# CORE.net
KiCad netlist of a schematic drawn in Altium Designer
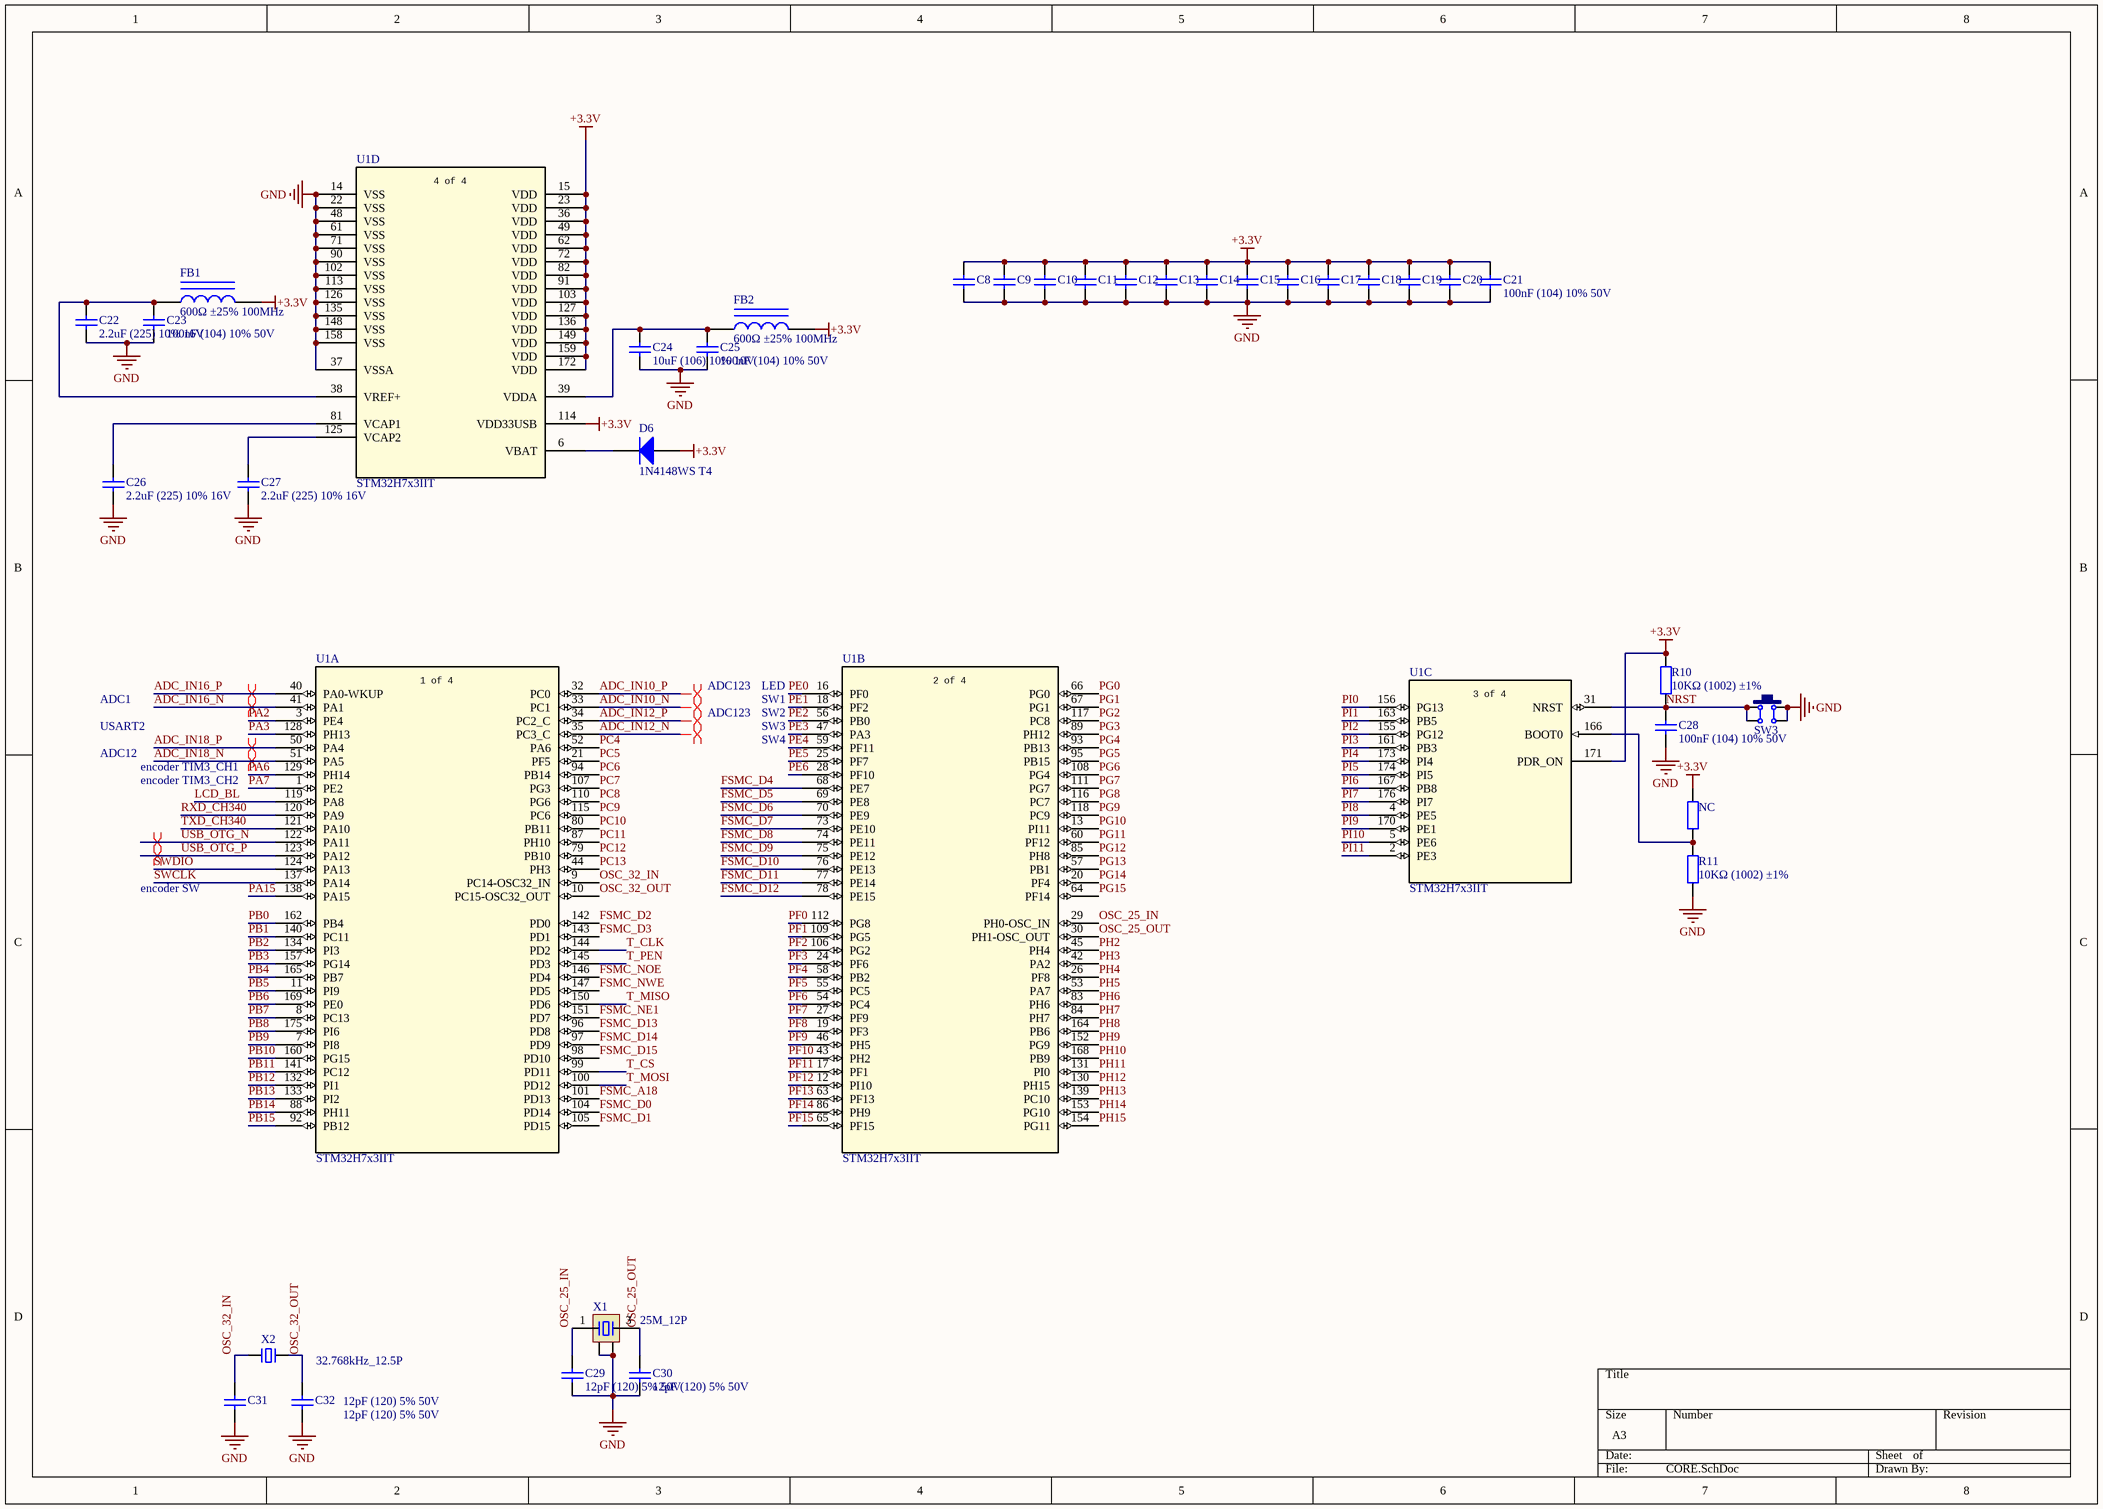
[diagram p0: CORE.SchDoc]

(export (version "E")
  (design (tool "Eeschema 10.0.6"))
  (components
    (comp (ref "C8")
      (value "100nF (104) 10% 50V")
      (footprint "0603_C")
      (description "贴片电容")
      (libsource (lib "Cap") (part "0603 100nF (104) 10% 50V"))
    )
    (comp (ref "C9")
      (value "100nF (104) 10% 50V")
      (footprint "0603_C")
      (description "贴片电容")
      (libsource (lib "Cap") (part "0603 100nF (104) 10% 50V"))
    )
    (comp (ref "C10")
      (value "100nF (104) 10% 50V")
      (footprint "0603_C")
      (description "贴片电容")
      (libsource (lib "Cap") (part "0603 100nF (104) 10% 50V"))
    )
    (comp (ref "C11")
      (value "100nF (104) 10% 50V")
      (footprint "0603_C")
      (description "贴片电容")
      (libsource (lib "Cap") (part "0603 100nF (104) 10% 50V"))
    )
    (comp (ref "C12")
      (value "100nF (104) 10% 50V")
      (footprint "0603_C")
      (description "贴片电容")
      (libsource (lib "Cap") (part "0603 100nF (104) 10% 50V"))
    )
    (comp (ref "C13")
      (value "100nF (104) 10% 50V")
      (footprint "0603_C")
      (description "贴片电容")
      (libsource (lib "Cap") (part "0603 100nF (104) 10% 50V"))
    )
    (comp (ref "C14")
      (value "100nF (104) 10% 50V")
      (footprint "0603_C")
      (description "贴片电容")
      (libsource (lib "Cap") (part "0603 100nF (104) 10% 50V"))
    )
    (comp (ref "C15")
      (value "100nF (104) 10% 50V")
      (footprint "0603_C")
      (description "贴片电容")
      (libsource (lib "Cap") (part "0603 100nF (104) 10% 50V"))
    )
    (comp (ref "C16")
      (value "100nF (104) 10% 50V")
      (footprint "0603_C")
      (description "贴片电容")
      (libsource (lib "Cap") (part "0603 100nF (104) 10% 50V"))
    )
    (comp (ref "C17")
      (value "100nF (104) 10% 50V")
      (footprint "0603_C")
      (description "贴片电容")
      (libsource (lib "Cap") (part "0603 100nF (104) 10% 50V"))
    )
    (comp (ref "C18")
      (value "100nF (104) 10% 50V")
      (footprint "0603_C")
      (description "贴片电容")
      (libsource (lib "Cap") (part "0603 100nF (104) 10% 50V"))
    )
    (comp (ref "C19")
      (value "100nF (104) 10% 50V")
      (footprint "0603_C")
      (description "贴片电容")
      (libsource (lib "Cap") (part "0603 100nF (104) 10% 50V"))
    )
    (comp (ref "C20")
      (value "100nF (104) 10% 50V")
      (footprint "0603_C")
      (description "贴片电容")
      (libsource (lib "Cap") (part "0603 100nF (104) 10% 50V"))
    )
    (comp (ref "C21")
      (value "100nF (104) 10% 50V")
      (footprint "0603_C")
      (description "贴片电容")
      (libsource (lib "Cap") (part "0603 100nF (104) 10% 50V"))
    )
    (comp (ref "C22")
      (value "2.2uF (225) 10% 16V")
      (footprint "0603_C")
      (description "贴片电容")
      (libsource (lib "Cap") (part "0603 2.2uF (225) 10% 16V"))
    )
    (comp (ref "C23")
      (value "100nF (104) 10% 50V")
      (footprint "0603_C")
      (description "贴片电容")
      (libsource (lib "Cap") (part "0603 100nF (104) 10% 50V"))
    )
    (comp (ref "C24")
      (value "10uF (106) 10% 10V")
      (footprint "0603_C")
      (description "贴片电容")
      (libsource (lib "Cap") (part "0603 10uF (106) 10% 10V"))
    )
    (comp (ref "C25")
      (value "100nF (104) 10% 50V")
      (footprint "0603_C")
      (description "贴片电容")
      (libsource (lib "Cap") (part "0603 100nF (104) 10% 50V"))
    )
    (comp (ref "C26")
      (value "2.2uF (225) 10% 16V")
      (footprint "0603_C")
      (description "贴片电容")
      (libsource (lib "Cap") (part "0603 2.2uF (225) 10% 16V"))
    )
    (comp (ref "C27")
      (value "2.2uF (225) 10% 16V")
      (footprint "0603_C")
      (description "贴片电容")
      (libsource (lib "Cap") (part "0603 2.2uF (225) 10% 16V"))
    )
    (comp (ref "C28")
      (value "100nF (104) 10% 50V")
      (footprint "0603_C")
      (description "贴片电容")
      (libsource (lib "Cap") (part "0603 100nF (104) 10% 50V"))
    )
    (comp (ref "C29")
      (value "12pF (120) 5% 50V")
      (footprint "0603_C")
      (description "贴片电容")
      (libsource (lib "Cap") (part "0603 12pF (120) 5% 50V"))
    )
    (comp (ref "C30")
      (value "12pF (120) 5% 50V")
      (footprint "0603_C")
      (description "贴片电容")
      (libsource (lib "Cap") (part "0603 12pF (120) 5% 50V"))
    )
    (comp (ref "C31")
      (value "12pF (120) 5% 50V")
      (footprint "0603_C")
      (description "贴片电容")
      (libsource (lib "Cap") (part "0603 12pF (120) 5% 50V"))
    )
    (comp (ref "C32")
      (value "12pF (120) 5% 50V")
      (footprint "0603_C")
      (description "贴片电容")
      (libsource (lib "Cap") (part "0603 12pF (120) 5% 50V"))
    )
    (comp (ref "D6")
      (value "1N4148WS T4")
      (footprint "SOD-323")
      (description "二极管")
      (libsource (lib "Diode") (part "SOD-323 1N4148WS T4"))
    )
    (comp (ref "FB1")
      (value "600Ω ±25% 100MHz")
      (footprint "0805_L")
      (description "贴片磁珠")
      (libsource (lib "IUD") (part "0805 600Ω 25% 100MHz"))
    )
    (comp (ref "FB2")
      (value "600Ω ±25% 100MHz")
      (footprint "0805_L")
      (description "贴片磁珠")
      (libsource (lib "IUD") (part "0805 600Ω 25% 100MHz"))
    )
    (comp (ref "NC")
      (value "~")
      (footprint "0603_R")
      (description "贴片电阻")
      (libsource (lib "RES") (part "0603 0Ω (0R0) 1%"))
    )
    (comp (ref "R10")
      (value "10KΩ (1002) ±1%")
      (footprint "0603_R")
      (description "贴片电阻")
      (libsource (lib "RES") (part "0603 10KΩ (1002) 1%"))
    )
    (comp (ref "R11")
      (value "10KΩ (1002) ±1%")
      (footprint "0603_R")
      (description "贴片电阻")
      (libsource (lib "RES") (part "0603 10KΩ (1002) 1%"))
    )
    (comp (ref "SW3")
      (value "6x6x5")
      (footprint "TSW DIP-6*6*6")
      (description "直插6x6轻触开关")
      (fields (field (name "版权归属") "源创客"))
      (libsource (lib "5.1   - 按键-开关") (part "TSW DIP-6x6"))
    )
    (comp (ref "U1")
      (value "STM32H7x3IIT")
      (footprint "LQFP176_24x24mm")
      (description "Imported")
      (fields
        (field (name "MANUFACTURER_PART_NUMBER") "stm32h7x3iit")
        (field (name "COPYRIGHT") "Copyright (C) 2016 Accelerated Designs. All rights reserved")
      )
      (libsource (lib "") (part "STM32H7x3IIT_3"))
    )
    (comp (ref "X1")
      (value "25M_12P")
      (footprint "OSC 3225-4P")
      (description "4脚无源晶振")
      (fields (field (name "版权归属") "源创客"))
      (libsource (lib "10.1 - 保险丝-晶振") (part "XTAL-4P"))
    )
    (comp (ref "X2")
      (value "32.768kHz_12.5P")
      (footprint "OSC 3215-2P")
      (description "2脚无源脚晶振")
      (fields (field (name "版权归属") "源创客"))
      (libsource (lib "10.1 - 保险丝-晶振") (part "XTAL-2P"))
    )
  )
  (nets
    (net (code "1") (name "+3.3V") (class "Default")
      (node (ref "C10") (pin "2") (pinfunction "2_2") (pintype "passive"))
      (node (ref "C11") (pin "2") (pinfunction "2_2") (pintype "passive"))
      (node (ref "C12") (pin "2") (pinfunction "2_2") (pintype "passive"))
      (node (ref "C13") (pin "2") (pinfunction "2_2") (pintype "passive"))
      (node (ref "C14") (pin "2") (pinfunction "2_2") (pintype "passive"))
      (node (ref "C15") (pin "2") (pinfunction "2_2") (pintype "passive"))
      (node (ref "C16") (pin "2") (pinfunction "2_2") (pintype "passive"))
      (node (ref "C17") (pin "2") (pinfunction "2_2") (pintype "passive"))
      (node (ref "C18") (pin "2") (pinfunction "2_2") (pintype "passive"))
      (node (ref "C19") (pin "2") (pinfunction "2_2") (pintype "passive"))
      (node (ref "C20") (pin "2") (pinfunction "2_2") (pintype "passive"))
      (node (ref "C21") (pin "2") (pinfunction "2_2") (pintype "passive"))
      (node (ref "C8") (pin "2") (pinfunction "2_2") (pintype "passive"))
      (node (ref "C9") (pin "2") (pinfunction "2_2") (pintype "passive"))
      (node (ref "D6") (pin "1") (pinfunction "A_1") (pintype "passive"))
      (node (ref "FB1") (pin "2") (pinfunction "2_2") (pintype "passive"))
      (node (ref "FB2") (pin "2") (pinfunction "2_2") (pintype "passive"))
      (node (ref "NC") (pin "1") (pinfunction "1_1") (pintype "passive"))
      (node (ref "R10") (pin "2") (pinfunction "2_2") (pintype "passive"))
      (node (ref "U1") (pin "103") (pinfunction "VDD_103") (pintype "power_in"))
      (node (ref "U1") (pin "114") (pinfunction "VDD33USB_114") (pintype "power_in"))
      (node (ref "U1") (pin "127") (pinfunction "VDD_127") (pintype "power_in"))
      (node (ref "U1") (pin "136") (pinfunction "VDD_136") (pintype "power_in"))
      (node (ref "U1") (pin "149") (pinfunction "VDD_149") (pintype "power_in"))
      (node (ref "U1") (pin "15") (pinfunction "VDD_15") (pintype "power_in"))
      (node (ref "U1") (pin "159") (pinfunction "VDD_159") (pintype "power_in"))
      (node (ref "U1") (pin "171") (pinfunction "PDR_ON_171") (pintype "passive"))
      (node (ref "U1") (pin "172") (pinfunction "VDD_172") (pintype "power_in"))
      (node (ref "U1") (pin "23") (pinfunction "VDD_23") (pintype "power_in"))
      (node (ref "U1") (pin "36") (pinfunction "VDD_36") (pintype "power_in"))
      (node (ref "U1") (pin "49") (pinfunction "VDD_49") (pintype "power_in"))
      (node (ref "U1") (pin "62") (pinfunction "VDD_62") (pintype "power_in"))
      (node (ref "U1") (pin "72") (pinfunction "VDD_72") (pintype "power_in"))
      (node (ref "U1") (pin "82") (pinfunction "VDD_82") (pintype "power_in"))
      (node (ref "U1") (pin "91") (pinfunction "VDD_91") (pintype "power_in"))
    )
    (net (code "2") (name "/ADC_IN10_N") (class "Default")
      (node (ref "U1") (pin "33") (pinfunction "PC1_33") (pintype "bidirectional"))
    )
    (net (code "3") (name "/ADC_IN10_P") (class "Default")
      (node (ref "U1") (pin "32") (pinfunction "PC0_32") (pintype "bidirectional"))
    )
    (net (code "4") (name "/ADC_IN12_N") (class "Default")
      (node (ref "U1") (pin "35") (pinfunction "PC3_C_35") (pintype "bidirectional"))
    )
    (net (code "5") (name "/ADC_IN12_P") (class "Default")
      (node (ref "U1") (pin "34") (pinfunction "PC2_C_34") (pintype "bidirectional"))
    )
    (net (code "6") (name "/ADC_IN16_N") (class "Default")
      (node (ref "U1") (pin "41") (pinfunction "PA1_41") (pintype "bidirectional"))
    )
    (net (code "7") (name "/ADC_IN16_P") (class "Default")
      (node (ref "U1") (pin "40") (pinfunction "PA0-WKUP_40") (pintype "bidirectional"))
    )
    (net (code "8") (name "/ADC_IN18_N") (class "Default")
      (node (ref "U1") (pin "51") (pinfunction "PA5_51") (pintype "bidirectional"))
    )
    (net (code "9") (name "/ADC_IN18_P") (class "Default")
      (node (ref "U1") (pin "50") (pinfunction "PA4_50") (pintype "bidirectional"))
    )
    (net (code "10") (name "/FSMC_A18") (class "Default")
      (node (ref "U1") (pin "101") (pinfunction "PD13_101") (pintype "bidirectional"))
    )
    (net (code "11") (name "/FSMC_D0") (class "Default")
      (node (ref "U1") (pin "104") (pinfunction "PD14_104") (pintype "bidirectional"))
    )
    (net (code "12") (name "/FSMC_D1") (class "Default")
      (node (ref "U1") (pin "105") (pinfunction "PD15_105") (pintype "bidirectional"))
    )
    (net (code "13") (name "/FSMC_D2") (class "Default")
      (node (ref "U1") (pin "142") (pinfunction "PD0_142") (pintype "bidirectional"))
    )
    (net (code "14") (name "/FSMC_D3") (class "Default")
      (node (ref "U1") (pin "143") (pinfunction "PD1_143") (pintype "bidirectional"))
    )
    (net (code "15") (name "/FSMC_D4") (class "Default")
      (node (ref "U1") (pin "68") (pinfunction "PE7_68") (pintype "bidirectional"))
    )
    (net (code "16") (name "/FSMC_D5") (class "Default")
      (node (ref "U1") (pin "69") (pinfunction "PE8_69") (pintype "bidirectional"))
    )
    (net (code "17") (name "/FSMC_D6") (class "Default")
      (node (ref "U1") (pin "70") (pinfunction "PE9_70") (pintype "bidirectional"))
    )
    (net (code "18") (name "/FSMC_D7") (class "Default")
      (node (ref "U1") (pin "73") (pinfunction "PE10_73") (pintype "bidirectional"))
    )
    (net (code "19") (name "/FSMC_D8") (class "Default")
      (node (ref "U1") (pin "74") (pinfunction "PE11_74") (pintype "bidirectional"))
    )
    (net (code "20") (name "/FSMC_D9") (class "Default")
      (node (ref "U1") (pin "75") (pinfunction "PE12_75") (pintype "bidirectional"))
    )
    (net (code "21") (name "/FSMC_D10") (class "Default")
      (node (ref "U1") (pin "76") (pinfunction "PE13_76") (pintype "bidirectional"))
    )
    (net (code "22") (name "/FSMC_D11") (class "Default")
      (node (ref "U1") (pin "77") (pinfunction "PE14_77") (pintype "bidirectional"))
    )
    (net (code "23") (name "/FSMC_D12") (class "Default")
      (node (ref "U1") (pin "78") (pinfunction "PE15_78") (pintype "bidirectional"))
    )
    (net (code "24") (name "/FSMC_D13") (class "Default")
      (node (ref "U1") (pin "96") (pinfunction "PD8_96") (pintype "bidirectional"))
    )
    (net (code "25") (name "/FSMC_D14") (class "Default")
      (node (ref "U1") (pin "97") (pinfunction "PD9_97") (pintype "bidirectional"))
    )
    (net (code "26") (name "/FSMC_D15") (class "Default")
      (node (ref "U1") (pin "98") (pinfunction "PD10_98") (pintype "bidirectional"))
    )
    (net (code "27") (name "/FSMC_NE1") (class "Default")
      (node (ref "U1") (pin "151") (pinfunction "PD7_151") (pintype "bidirectional"))
    )
    (net (code "28") (name "/FSMC_NOE") (class "Default")
      (node (ref "U1") (pin "146") (pinfunction "PD4_146") (pintype "bidirectional"))
    )
    (net (code "29") (name "/FSMC_NWE") (class "Default")
      (node (ref "U1") (pin "147") (pinfunction "PD5_147") (pintype "bidirectional"))
    )
    (net (code "30") (name "/LCD_BL") (class "Default")
      (node (ref "U1") (pin "119") (pinfunction "PA8_119") (pintype "bidirectional"))
    )
    (net (code "31") (name "/NRST") (class "Default")
      (node (ref "C28") (pin "2") (pinfunction "2_2") (pintype "passive"))
      (node (ref "R10") (pin "1") (pinfunction "1_1") (pintype "passive"))
      (node (ref "SW3") (pin "1") (pinfunction "1_1") (pintype "passive"))
      (node (ref "SW3") (pin "4") (pinfunction "4_4") (pintype "passive"))
      (node (ref "U1") (pin "31") (pinfunction "NRST_31") (pintype "bidirectional"))
    )
    (net (code "32") (name "/OSC_25_IN") (class "Default")
      (node (ref "C29") (pin "2") (pinfunction "2_2") (pintype "passive"))
      (node (ref "U1") (pin "29") (pinfunction "PH0-OSC_IN_29") (pintype "bidirectional"))
      (node (ref "X1") (pin "1") (pinfunction "1_1") (pintype "passive"))
    )
    (net (code "33") (name "/OSC_25_OUT") (class "Default")
      (node (ref "C30") (pin "1") (pinfunction "1_1") (pintype "passive"))
      (node (ref "U1") (pin "30") (pinfunction "PH1-OSC_OUT_30") (pintype "bidirectional"))
      (node (ref "X1") (pin "3") (pinfunction "3_3") (pintype "passive"))
    )
    (net (code "34") (name "/OSC_32_IN") (class "Default")
      (node (ref "C31") (pin "2") (pinfunction "2_2") (pintype "passive"))
      (node (ref "U1") (pin "9") (pinfunction "PC14-OSC32_IN_9") (pintype "bidirectional"))
      (node (ref "X2") (pin "1") (pinfunction "1_1") (pintype "passive"))
    )
    (net (code "35") (name "/OSC_32_OUT") (class "Default")
      (node (ref "C32") (pin "2") (pinfunction "2_2") (pintype "passive"))
      (node (ref "U1") (pin "10") (pinfunction "PC15-OSC32_OUT_10") (pintype "bidirectional"))
      (node (ref "X2") (pin "2") (pinfunction "2_2") (pintype "passive"))
    )
    (net (code "36") (name "/PA2") (class "Default")
      (node (ref "U1") (pin "3") (pinfunction "PE4_3") (pintype "bidirectional"))
    )
    (net (code "37") (name "/PA3") (class "Default")
      (node (ref "U1") (pin "128") (pinfunction "PH13_128") (pintype "bidirectional"))
    )
    (net (code "38") (name "/PA6") (class "Default")
      (node (ref "U1") (pin "129") (pinfunction "PH14_129") (pintype "bidirectional"))
    )
    (net (code "39") (name "/PA7") (class "Default")
      (node (ref "U1") (pin "1") (pinfunction "PE2_1") (pintype "bidirectional"))
    )
    (net (code "40") (name "/PA15") (class "Default")
      (node (ref "U1") (pin "138") (pinfunction "PA15_138") (pintype "bidirectional"))
    )
    (net (code "41") (name "/PB0") (class "Default")
      (node (ref "U1") (pin "162") (pinfunction "PB4_162") (pintype "bidirectional"))
    )
    (net (code "42") (name "/PB1") (class "Default")
      (node (ref "U1") (pin "140") (pinfunction "PC11_140") (pintype "bidirectional"))
    )
    (net (code "43") (name "/PB2") (class "Default")
      (node (ref "U1") (pin "134") (pinfunction "PI3_134") (pintype "bidirectional"))
    )
    (net (code "44") (name "/PB3") (class "Default")
      (node (ref "U1") (pin "157") (pinfunction "PG14_157") (pintype "bidirectional"))
    )
    (net (code "45") (name "/PB4") (class "Default")
      (node (ref "U1") (pin "165") (pinfunction "PB7_165") (pintype "bidirectional"))
    )
    (net (code "46") (name "/PB5") (class "Default")
      (node (ref "U1") (pin "11") (pinfunction "PI9_11") (pintype "bidirectional"))
    )
    (net (code "47") (name "/PB6") (class "Default")
      (node (ref "U1") (pin "169") (pinfunction "PE0_169") (pintype "bidirectional"))
    )
    (net (code "48") (name "/PB7") (class "Default")
      (node (ref "U1") (pin "8") (pinfunction "PC13_8") (pintype "bidirectional"))
    )
    (net (code "49") (name "/PB8") (class "Default")
      (node (ref "U1") (pin "175") (pinfunction "PI6_175") (pintype "bidirectional"))
    )
    (net (code "50") (name "/PB9") (class "Default")
      (node (ref "U1") (pin "7") (pinfunction "PI8_7") (pintype "bidirectional"))
    )
    (net (code "51") (name "/PB10") (class "Default")
      (node (ref "U1") (pin "160") (pinfunction "PG15_160") (pintype "bidirectional"))
    )
    (net (code "52") (name "/PB11") (class "Default")
      (node (ref "U1") (pin "141") (pinfunction "PC12_141") (pintype "bidirectional"))
    )
    (net (code "53") (name "/PB12") (class "Default")
      (node (ref "U1") (pin "132") (pinfunction "PI1_132") (pintype "bidirectional"))
    )
    (net (code "54") (name "/PB13") (class "Default")
      (node (ref "U1") (pin "133") (pinfunction "PI2_133") (pintype "bidirectional"))
    )
    (net (code "55") (name "/PB14") (class "Default")
      (node (ref "U1") (pin "88") (pinfunction "PH11_88") (pintype "bidirectional"))
    )
    (net (code "56") (name "/PB15") (class "Default")
      (node (ref "U1") (pin "92") (pinfunction "PB12_92") (pintype "bidirectional"))
    )
    (net (code "57") (name "/PC4") (class "Default")
      (node (ref "U1") (pin "52") (pinfunction "PA6_52") (pintype "bidirectional"))
    )
    (net (code "58") (name "/PC5") (class "Default")
      (node (ref "U1") (pin "21") (pinfunction "PF5_21") (pintype "bidirectional"))
    )
    (net (code "59") (name "/PC6") (class "Default")
      (node (ref "U1") (pin "94") (pinfunction "PB14_94") (pintype "bidirectional"))
    )
    (net (code "60") (name "/PC7") (class "Default")
      (node (ref "U1") (pin "107") (pinfunction "PG3_107") (pintype "bidirectional"))
    )
    (net (code "61") (name "/PC8") (class "Default")
      (node (ref "U1") (pin "110") (pinfunction "PG6_110") (pintype "bidirectional"))
    )
    (net (code "62") (name "/PC9") (class "Default")
      (node (ref "U1") (pin "115") (pinfunction "PC6_115") (pintype "bidirectional"))
    )
    (net (code "63") (name "/PC10") (class "Default")
      (node (ref "U1") (pin "80") (pinfunction "PB11_80") (pintype "bidirectional"))
    )
    (net (code "64") (name "/PC11") (class "Default")
      (node (ref "U1") (pin "87") (pinfunction "PH10_87") (pintype "bidirectional"))
    )
    (net (code "65") (name "/PC12") (class "Default")
      (node (ref "U1") (pin "79") (pinfunction "PB10_79") (pintype "bidirectional"))
    )
    (net (code "66") (name "/PC13") (class "Default")
      (node (ref "U1") (pin "44") (pinfunction "PH3_44") (pintype "bidirectional"))
    )
    (net (code "67") (name "/PE0") (class "Default")
      (node (ref "U1") (pin "16") (pinfunction "PF0_16") (pintype "bidirectional"))
    )
    (net (code "68") (name "/PE1") (class "Default")
      (node (ref "U1") (pin "18") (pinfunction "PF2_18") (pintype "bidirectional"))
    )
    (net (code "69") (name "/PE2") (class "Default")
      (node (ref "U1") (pin "56") (pinfunction "PB0_56") (pintype "bidirectional"))
    )
    (net (code "70") (name "/PE3") (class "Default")
      (node (ref "U1") (pin "47") (pinfunction "PA3_47") (pintype "bidirectional"))
    )
    (net (code "71") (name "/PE4") (class "Default")
      (node (ref "U1") (pin "59") (pinfunction "PF11_59") (pintype "bidirectional"))
    )
    (net (code "72") (name "/PE5") (class "Default")
      (node (ref "U1") (pin "25") (pinfunction "PF7_25") (pintype "bidirectional"))
    )
    (net (code "73") (name "/PE6") (class "Default")
      (node (ref "U1") (pin "28") (pinfunction "PF10_28") (pintype "bidirectional"))
    )
    (net (code "74") (name "/PF0") (class "Default")
      (node (ref "U1") (pin "112") (pinfunction "PG8_112") (pintype "bidirectional"))
    )
    (net (code "75") (name "/PF1") (class "Default")
      (node (ref "U1") (pin "109") (pinfunction "PG5_109") (pintype "bidirectional"))
    )
    (net (code "76") (name "/PF2") (class "Default")
      (node (ref "U1") (pin "106") (pinfunction "PG2_106") (pintype "bidirectional"))
    )
    (net (code "77") (name "/PF3") (class "Default")
      (node (ref "U1") (pin "24") (pinfunction "PF6_24") (pintype "bidirectional"))
    )
    (net (code "78") (name "/PF4") (class "Default")
      (node (ref "U1") (pin "58") (pinfunction "PB2_58") (pintype "bidirectional"))
    )
    (net (code "79") (name "/PF5") (class "Default")
      (node (ref "U1") (pin "55") (pinfunction "PC5_55") (pintype "bidirectional"))
    )
    (net (code "80") (name "/PF6") (class "Default")
      (node (ref "U1") (pin "54") (pinfunction "PC4_54") (pintype "bidirectional"))
    )
    (net (code "81") (name "/PF7") (class "Default")
      (node (ref "U1") (pin "27") (pinfunction "PF9_27") (pintype "bidirectional"))
    )
    (net (code "82") (name "/PF8") (class "Default")
      (node (ref "U1") (pin "19") (pinfunction "PF3_19") (pintype "bidirectional"))
    )
    (net (code "83") (name "/PF9") (class "Default")
      (node (ref "U1") (pin "46") (pinfunction "PH5_46") (pintype "bidirectional"))
    )
    (net (code "84") (name "/PF10") (class "Default")
      (node (ref "U1") (pin "43") (pinfunction "PH2_43") (pintype "bidirectional"))
    )
    (net (code "85") (name "/PF11") (class "Default")
      (node (ref "U1") (pin "17") (pinfunction "PF1_17") (pintype "bidirectional"))
    )
    (net (code "86") (name "/PF12") (class "Default")
      (node (ref "U1") (pin "12") (pinfunction "PI10_12") (pintype "bidirectional"))
    )
    (net (code "87") (name "/PF13") (class "Default")
      (node (ref "U1") (pin "63") (pinfunction "PF13_63") (pintype "bidirectional"))
    )
    (net (code "88") (name "/PF14") (class "Default")
      (node (ref "U1") (pin "86") (pinfunction "PH9_86") (pintype "bidirectional"))
    )
    (net (code "89") (name "/PF15") (class "Default")
      (node (ref "U1") (pin "65") (pinfunction "PF15_65") (pintype "bidirectional"))
    )
    (net (code "90") (name "/PG0") (class "Default")
      (node (ref "U1") (pin "66") (pinfunction "PG0_66") (pintype "bidirectional"))
    )
    (net (code "91") (name "/PG1") (class "Default")
      (node (ref "U1") (pin "67") (pinfunction "PG1_67") (pintype "bidirectional"))
    )
    (net (code "92") (name "/PG2") (class "Default")
      (node (ref "U1") (pin "117") (pinfunction "PC8_117") (pintype "bidirectional"))
    )
    (net (code "93") (name "/PG3") (class "Default")
      (node (ref "U1") (pin "89") (pinfunction "PH12_89") (pintype "bidirectional"))
    )
    (net (code "94") (name "/PG4") (class "Default")
      (node (ref "U1") (pin "93") (pinfunction "PB13_93") (pintype "bidirectional"))
    )
    (net (code "95") (name "/PG5") (class "Default")
      (node (ref "U1") (pin "95") (pinfunction "PB15_95") (pintype "bidirectional"))
    )
    (net (code "96") (name "/PG6") (class "Default")
      (node (ref "U1") (pin "108") (pinfunction "PG4_108") (pintype "bidirectional"))
    )
    (net (code "97") (name "/PG7") (class "Default")
      (node (ref "U1") (pin "111") (pinfunction "PG7_111") (pintype "bidirectional"))
    )
    (net (code "98") (name "/PG8") (class "Default")
      (node (ref "U1") (pin "116") (pinfunction "PC7_116") (pintype "bidirectional"))
    )
    (net (code "99") (name "/PG9") (class "Default")
      (node (ref "U1") (pin "118") (pinfunction "PC9_118") (pintype "bidirectional"))
    )
    (net (code "100") (name "/PG10") (class "Default")
      (node (ref "U1") (pin "13") (pinfunction "PI11_13") (pintype "bidirectional"))
    )
    (net (code "101") (name "/PG11") (class "Default")
      (node (ref "U1") (pin "60") (pinfunction "PF12_60") (pintype "bidirectional"))
    )
    (net (code "102") (name "/PG12") (class "Default")
      (node (ref "U1") (pin "85") (pinfunction "PH8_85") (pintype "bidirectional"))
    )
    (net (code "103") (name "/PG13") (class "Default")
      (node (ref "U1") (pin "57") (pinfunction "PB1_57") (pintype "bidirectional"))
    )
    (net (code "104") (name "/PG14") (class "Default")
      (node (ref "U1") (pin "20") (pinfunction "PF4_20") (pintype "bidirectional"))
    )
    (net (code "105") (name "/PG15") (class "Default")
      (node (ref "U1") (pin "64") (pinfunction "PF14_64") (pintype "bidirectional"))
    )
    (net (code "106") (name "/PH2") (class "Default")
      (node (ref "U1") (pin "45") (pinfunction "PH4_45") (pintype "bidirectional"))
    )
    (net (code "107") (name "/PH3") (class "Default")
      (node (ref "U1") (pin "42") (pinfunction "PA2_42") (pintype "bidirectional"))
    )
    (net (code "108") (name "/PH4") (class "Default")
      (node (ref "U1") (pin "26") (pinfunction "PF8_26") (pintype "bidirectional"))
    )
    (net (code "109") (name "/PH5") (class "Default")
      (node (ref "U1") (pin "53") (pinfunction "PA7_53") (pintype "bidirectional"))
    )
    (net (code "110") (name "/PH6") (class "Default")
      (node (ref "U1") (pin "83") (pinfunction "PH6_83") (pintype "bidirectional"))
    )
    (net (code "111") (name "/PH7") (class "Default")
      (node (ref "U1") (pin "84") (pinfunction "PH7_84") (pintype "bidirectional"))
    )
    (net (code "112") (name "/PH8") (class "Default")
      (node (ref "U1") (pin "164") (pinfunction "PB6_164") (pintype "bidirectional"))
    )
    (net (code "113") (name "/PH9") (class "Default")
      (node (ref "U1") (pin "152") (pinfunction "PG9_152") (pintype "bidirectional"))
    )
    (net (code "114") (name "/PH10") (class "Default")
      (node (ref "U1") (pin "168") (pinfunction "PB9_168") (pintype "bidirectional"))
    )
    (net (code "115") (name "/PH11") (class "Default")
      (node (ref "U1") (pin "131") (pinfunction "PI0_131") (pintype "bidirectional"))
    )
    (net (code "116") (name "/PH12") (class "Default")
      (node (ref "U1") (pin "130") (pinfunction "PH15_130") (pintype "bidirectional"))
    )
    (net (code "117") (name "/PH13") (class "Default")
      (node (ref "U1") (pin "139") (pinfunction "PC10_139") (pintype "bidirectional"))
    )
    (net (code "118") (name "/PH14") (class "Default")
      (node (ref "U1") (pin "153") (pinfunction "PG10_153") (pintype "bidirectional"))
    )
    (net (code "119") (name "/PH15") (class "Default")
      (node (ref "U1") (pin "154") (pinfunction "PG11_154") (pintype "bidirectional"))
    )
    (net (code "120") (name "/PI0") (class "Default")
      (node (ref "U1") (pin "156") (pinfunction "PG13_156") (pintype "bidirectional"))
    )
    (net (code "121") (name "/PI1") (class "Default")
      (node (ref "U1") (pin "163") (pinfunction "PB5_163") (pintype "bidirectional"))
    )
    (net (code "122") (name "/PI2") (class "Default")
      (node (ref "U1") (pin "155") (pinfunction "PG12_155") (pintype "bidirectional"))
    )
    (net (code "123") (name "/PI3") (class "Default")
      (node (ref "U1") (pin "161") (pinfunction "PB3_161") (pintype "bidirectional"))
    )
    (net (code "124") (name "/PI4") (class "Default")
      (node (ref "U1") (pin "173") (pinfunction "PI4_173") (pintype "bidirectional"))
    )
    (net (code "125") (name "/PI5") (class "Default")
      (node (ref "U1") (pin "174") (pinfunction "PI5_174") (pintype "bidirectional"))
    )
    (net (code "126") (name "/PI6") (class "Default")
      (node (ref "U1") (pin "167") (pinfunction "PB8_167") (pintype "bidirectional"))
    )
    (net (code "127") (name "/PI7") (class "Default")
      (node (ref "U1") (pin "176") (pinfunction "PI7_176") (pintype "bidirectional"))
    )
    (net (code "128") (name "/PI8") (class "Default")
      (node (ref "U1") (pin "4") (pinfunction "PE5_4") (pintype "bidirectional"))
    )
    (net (code "129") (name "/PI9") (class "Default")
      (node (ref "U1") (pin "170") (pinfunction "PE1_170") (pintype "bidirectional"))
    )
    (net (code "130") (name "/PI10") (class "Default")
      (node (ref "U1") (pin "5") (pinfunction "PE6_5") (pintype "bidirectional"))
    )
    (net (code "131") (name "/PI11") (class "Default")
      (node (ref "U1") (pin "2") (pinfunction "PE3_2") (pintype "bidirectional"))
    )
    (net (code "132") (name "/RXD_CH340") (class "Default")
      (node (ref "U1") (pin "120") (pinfunction "PA9_120") (pintype "bidirectional"))
    )
    (net (code "133") (name "/SWCLK") (class "Default")
      (node (ref "U1") (pin "137") (pinfunction "PA14_137") (pintype "bidirectional"))
    )
    (net (code "134") (name "/SWDIO") (class "Default")
      (node (ref "U1") (pin "124") (pinfunction "PA13_124") (pintype "bidirectional"))
    )
    (net (code "135") (name "/TXD_CH340") (class "Default")
      (node (ref "U1") (pin "121") (pinfunction "PA10_121") (pintype "bidirectional"))
    )
    (net (code "136") (name "/T_CLK") (class "Default")
      (node (ref "U1") (pin "144") (pinfunction "PD2_144") (pintype "bidirectional"))
    )
    (net (code "137") (name "/T_CS") (class "Default")
      (node (ref "U1") (pin "99") (pinfunction "PD11_99") (pintype "bidirectional"))
    )
    (net (code "138") (name "/T_MISO") (class "Default")
      (node (ref "U1") (pin "150") (pinfunction "PD6_150") (pintype "bidirectional"))
    )
    (net (code "139") (name "/T_MOSI") (class "Default")
      (node (ref "U1") (pin "100") (pinfunction "PD12_100") (pintype "bidirectional"))
    )
    (net (code "140") (name "/T_PEN") (class "Default")
      (node (ref "U1") (pin "145") (pinfunction "PD3_145") (pintype "bidirectional"))
    )
    (net (code "141") (name "/USB_OTG_N") (class "Default")
      (node (ref "U1") (pin "122") (pinfunction "PA11_122") (pintype "bidirectional"))
    )
    (net (code "142") (name "/USB_OTG_P") (class "Default")
      (node (ref "U1") (pin "123") (pinfunction "PA12_123") (pintype "bidirectional"))
    )
    (net (code "143") (name "GND") (class "Default")
      (node (ref "C10") (pin "1") (pinfunction "1_1") (pintype "passive"))
      (node (ref "C11") (pin "1") (pinfunction "1_1") (pintype "passive"))
      (node (ref "C12") (pin "1") (pinfunction "1_1") (pintype "passive"))
      (node (ref "C13") (pin "1") (pinfunction "1_1") (pintype "passive"))
      (node (ref "C14") (pin "1") (pinfunction "1_1") (pintype "passive"))
      (node (ref "C15") (pin "1") (pinfunction "1_1") (pintype "passive"))
      (node (ref "C16") (pin "1") (pinfunction "1_1") (pintype "passive"))
      (node (ref "C17") (pin "1") (pinfunction "1_1") (pintype "passive"))
      (node (ref "C18") (pin "1") (pinfunction "1_1") (pintype "passive"))
      (node (ref "C19") (pin "1") (pinfunction "1_1") (pintype "passive"))
      (node (ref "C20") (pin "1") (pinfunction "1_1") (pintype "passive"))
      (node (ref "C21") (pin "1") (pinfunction "1_1") (pintype "passive"))
      (node (ref "C22") (pin "1") (pinfunction "1_1") (pintype "passive"))
      (node (ref "C23") (pin "1") (pinfunction "1_1") (pintype "passive"))
      (node (ref "C24") (pin "1") (pinfunction "1_1") (pintype "passive"))
      (node (ref "C25") (pin "1") (pinfunction "1_1") (pintype "passive"))
      (node (ref "C26") (pin "1") (pinfunction "1_1") (pintype "passive"))
      (node (ref "C27") (pin "1") (pinfunction "1_1") (pintype "passive"))
      (node (ref "C28") (pin "1") (pinfunction "1_1") (pintype "passive"))
      (node (ref "C29") (pin "1") (pinfunction "1_1") (pintype "passive"))
      (node (ref "C30") (pin "2") (pinfunction "2_2") (pintype "passive"))
      (node (ref "C31") (pin "1") (pinfunction "1_1") (pintype "passive"))
      (node (ref "C32") (pin "1") (pinfunction "1_1") (pintype "passive"))
      (node (ref "C8") (pin "1") (pinfunction "1_1") (pintype "passive"))
      (node (ref "C9") (pin "1") (pinfunction "1_1") (pintype "passive"))
      (node (ref "R11") (pin "1") (pinfunction "1_1") (pintype "passive"))
      (node (ref "SW3") (pin "2") (pinfunction "2_2") (pintype "passive"))
      (node (ref "SW3") (pin "3") (pinfunction "3_3") (pintype "passive"))
      (node (ref "U1") (pin "102") (pinfunction "VSS_102") (pintype "power_in"))
      (node (ref "U1") (pin "113") (pinfunction "VSS_113") (pintype "power_in"))
      (node (ref "U1") (pin "126") (pinfunction "VSS_126") (pintype "power_in"))
      (node (ref "U1") (pin "135") (pinfunction "VSS_135") (pintype "power_in"))
      (node (ref "U1") (pin "14") (pinfunction "VSS_14") (pintype "power_in"))
      (node (ref "U1") (pin "148") (pinfunction "VSS_148") (pintype "power_in"))
      (node (ref "U1") (pin "158") (pinfunction "VSS_158") (pintype "power_in"))
      (node (ref "U1") (pin "22") (pinfunction "VSS_22") (pintype "power_in"))
      (node (ref "U1") (pin "37") (pinfunction "VSSA_37") (pintype "power_in"))
      (node (ref "U1") (pin "48") (pinfunction "VSS_48") (pintype "power_in"))
      (node (ref "U1") (pin "61") (pinfunction "VSS_61") (pintype "power_in"))
      (node (ref "U1") (pin "71") (pinfunction "VSS_71") (pintype "power_in"))
      (node (ref "U1") (pin "90") (pinfunction "VSS_90") (pintype "power_in"))
      (node (ref "X1") (pin "2") (pinfunction "2_2") (pintype "passive"))
      (node (ref "X1") (pin "4") (pinfunction "4_4") (pintype "passive"))
    )
    (net (code "144") (name "Net-(D6-K)") (class "Default")
      (node (ref "D6") (pin "2") (pinfunction "K_2") (pintype "passive"))
      (node (ref "U1") (pin "6") (pinfunction "VBAT_6") (pintype "power_in"))
    )
    (net (code "145") (name "Net-(U1C-BOOT0)") (class "Default")
      (node (ref "NC") (pin "2") (pinfunction "2_2") (pintype "passive"))
      (node (ref "R11") (pin "2") (pinfunction "2_2") (pintype "passive"))
      (node (ref "U1") (pin "166") (pinfunction "BOOT0_166") (pintype "input"))
    )
    (net (code "146") (name "Net-(U1D-VCAP1)") (class "Default")
      (node (ref "C26") (pin "2") (pinfunction "2_2") (pintype "passive"))
      (node (ref "U1") (pin "81") (pinfunction "VCAP1_81") (pintype "power_in"))
    )
    (net (code "147") (name "Net-(U1D-VCAP2)") (class "Default")
      (node (ref "C27") (pin "2") (pinfunction "2_2") (pintype "passive"))
      (node (ref "U1") (pin "125") (pinfunction "VCAP2_125") (pintype "power_in"))
    )
    (net (code "148") (name "Net-(U1D-VDDA)") (class "Default")
      (node (ref "C24") (pin "2") (pinfunction "2_2") (pintype "passive"))
      (node (ref "C25") (pin "2") (pinfunction "2_2") (pintype "passive"))
      (node (ref "FB2") (pin "1") (pinfunction "1_1") (pintype "passive"))
      (node (ref "U1") (pin "39") (pinfunction "VDDA_39") (pintype "power_in"))
    )
    (net (code "149") (name "Net-(U1D-VREF+)") (class "Default")
      (node (ref "C22") (pin "2") (pinfunction "2_2") (pintype "passive"))
      (node (ref "C23") (pin "2") (pinfunction "2_2") (pintype "passive"))
      (node (ref "FB1") (pin "1") (pinfunction "1_1") (pintype "passive"))
      (node (ref "U1") (pin "38") (pinfunction "VREF+_38") (pintype "power_in"))
    )
  )
)
